# 5V3AUSB.net
KiCad netlist of a schematic drawn in EAGLE
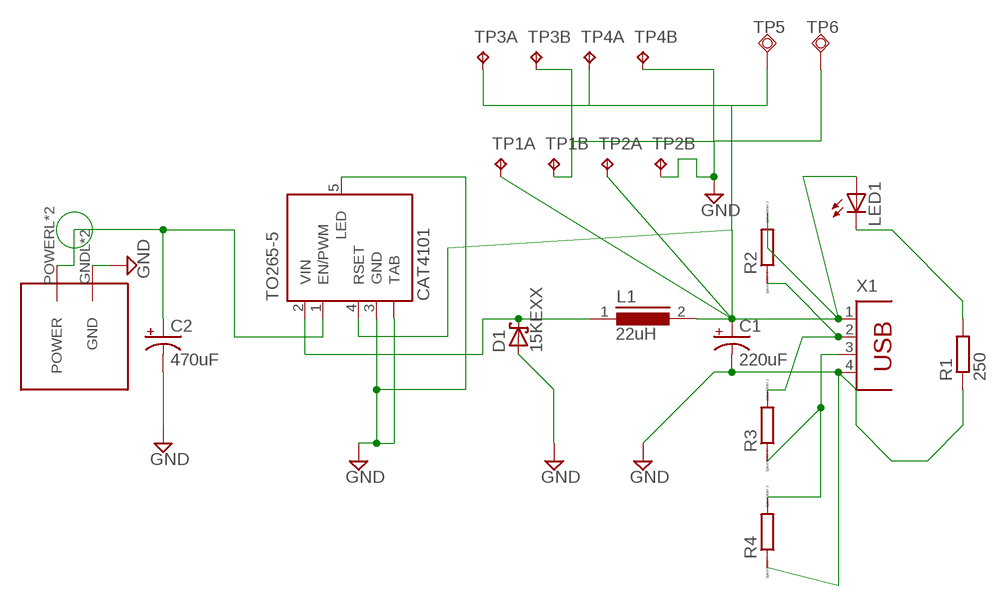
[diagram p0: schematic, sheet 1]

(export (version "E")
  (design (tool "Eeschema 10.0.6"))
  (components
    (comp (ref "C1")
      (value "220uF")
      (footprint "eagle-import:E2,5-6")
      (libsource (lib "eagle-import") (part "CPOL-USE2.5-6"))
    )
    (comp (ref "C2")
      (value "470uF")
      (footprint "eagle-import:E2,5-6")
      (libsource (lib "eagle-import") (part "CPOL-USE2.5-6"))
    )
    (comp (ref "D1")
      (value "15KEXX")
      (footprint "eagle-import:CB429-17")
      (libsource (lib "eagle-import") (part "15KEXX"))
    )
    (comp (ref "L1")
      (value "22uH")
      (footprint "eagle-import:SUKW3-27")
      (libsource (lib "eagle-import") (part "B82133"))
    )
    (comp (ref "LED1")
      (value "LEDCHIPLED_1206")
      (footprint "eagle-import:CHIPLED_1206")
      (libsource (lib "eagle-import") (part "LEDCHIPLED_1206"))
    )
    (comp (ref "R1")
      (value "250")
      (footprint "eagle-import:R1206")
      (libsource (lib "eagle-import") (part "R-EU_R1206"))
    )
    (comp (ref "R2")
      (value "R0204/7")
      (footprint "eagle-import:0204_7")
      (libsource (lib "eagle-import") (part "R0204/7"))
    )
    (comp (ref "R3")
      (value "R0204/7")
      (footprint "eagle-import:0204_7")
      (libsource (lib "eagle-import") (part "R0204/7"))
    )
    (comp (ref "R4")
      (value "R0204/7")
      (footprint "eagle-import:0204_7")
      (libsource (lib "eagle-import") (part "R0204/7"))
    )
    (comp (ref "TO265-5")
      (value "CAT4101")
      (footprint "eagle-import:TO263_5")
      (fields (field (name "MPN") "CAT4101TV-T75"))
      (libsource (lib "eagle-import") (part "CAT4101"))
    )
    (comp (ref "TP1")
      (value "TP2P2-38-20")
      (footprint "eagle-import:P2-38-20")
      (libsource (lib "eagle-import") (part "TP2P2-38-20"))
    )
    (comp (ref "TP2")
      (value "TP2P2-38-20")
      (footprint "eagle-import:P2-38-20")
      (libsource (lib "eagle-import") (part "TP2P2-38-20"))
    )
    (comp (ref "TP3")
      (value "TP2P2-38-20")
      (footprint "eagle-import:P2-38-20")
      (libsource (lib "eagle-import") (part "TP2P2-38-20"))
    )
    (comp (ref "TP4")
      (value "TP2P2-38-20")
      (footprint "eagle-import:P2-38-20")
      (libsource (lib "eagle-import") (part "TP2P2-38-20"))
    )
    (comp (ref "TP5")
      (value "TPSQTP20R")
      (footprint "eagle-import:TP20R")
      (libsource (lib "eagle-import") (part "TPSQTP20R"))
    )
    (comp (ref "TP6")
      (value "TPSQTP20R")
      (footprint "eagle-import:TP20R")
      (libsource (lib "eagle-import") (part "TPSQTP20R"))
    )
    (comp (ref "U$1")
      (value "2X2-MOLEX")
      (footprint "eagle-import:2X2MOLEX")
      (libsource (lib "eagle-import") (part "2X2-MOLEX"))
    )
    (comp (ref "X1")
      (value "PN87520")
      (footprint "eagle-import:PN87520")
      (libsource (lib "eagle-import") (part "PN87520"))
    )
  )
  (nets
    (net (code "1") (name "GND") (class "Default")
      (node (ref "C1") (pin "-") (pinfunction "-_-") (pintype "passive"))
      (node (ref "C2") (pin "-") (pinfunction "-_-") (pintype "passive"))
      (node (ref "D1") (pin "A") (pinfunction "A_A") (pintype "passive"))
      (node (ref "R1") (pin "1") (pinfunction "1_1") (pintype "passive"))
      (node (ref "R4") (pin "1") (pinfunction "1_1") (pintype "passive"))
      (node (ref "TO265-5") (pin "3") (pinfunction "GND_3") (pintype "power_in"))
      (node (ref "TO265-5") (pin "5") (pinfunction "LED_5") (pintype "power_in"))
      (node (ref "TO265-5") (pin "TAB") (pinfunction "TAB_TAB") (pintype "passive"))
      (node (ref "TP1") (pin "TP-2") (pinfunction "TP_TP-2") (pintype "input"))
      (node (ref "TP2") (pin "TP-2") (pinfunction "TP_TP-2") (pintype "input"))
      (node (ref "TP3") (pin "TP-2") (pinfunction "TP_TP-2") (pintype "input"))
      (node (ref "TP4") (pin "TP-2") (pinfunction "TP_TP-2") (pintype "input"))
      (node (ref "TP6") (pin "TP") (pinfunction "TP_TP") (pintype "input"))
      (node (ref "U$1") (pin "GNDL") (pinfunction "GND_GNDL") (pintype "bidirectional"))
      (node (ref "U$1") (pin "GNDR") (pinfunction "GND_GNDR") (pintype "bidirectional"))
      (node (ref "X1") (pin "4") (pinfunction "4_4") (pintype "passive"))
    )
    (net (code "2") (name "Net-(LED1-PadC)") (class "Default")
      (node (ref "LED1") (pin "C") (pinfunction "C_C") (pintype "passive"))
      (node (ref "R1") (pin "2") (pinfunction "2_2") (pintype "passive"))
    )
    (net (code "3") (name "Net-(R2-Pad1)") (class "Default")
      (node (ref "R2") (pin "1") (pinfunction "1_1") (pintype "passive"))
      (node (ref "R3") (pin "2") (pinfunction "2_2") (pintype "passive"))
      (node (ref "X1") (pin "2") (pinfunction "2_2") (pintype "passive"))
    )
    (net (code "4") (name "Net-(R3-Pad1)") (class "Default")
      (node (ref "R3") (pin "1") (pinfunction "1_1") (pintype "passive"))
      (node (ref "R4") (pin "2") (pinfunction "2_2") (pintype "passive"))
      (node (ref "X1") (pin "3") (pinfunction "3_3") (pintype "passive"))
    )
    (net (code "5") (name "Net-(TO265-5-EN{slash}PWM)") (class "Default")
      (node (ref "C2") (pin "+") (pinfunction "+_+") (pintype "passive"))
      (node (ref "TO265-5") (pin "1") (pinfunction "EN/PWM_1") (pintype "input"))
      (node (ref "U$1") (pin "POWERL") (pinfunction "POWER_POWERL") (pintype "bidirectional"))
      (node (ref "U$1") (pin "POWERR") (pinfunction "POWER_POWERR") (pintype "bidirectional"))
    )
    (net (code "6") (name "Net-(TO265-5-RSET)") (class "Default")
      (node (ref "C1") (pin "+") (pinfunction "+_+") (pintype "passive"))
      (node (ref "L1") (pin "2") (pinfunction "2_2") (pintype "passive"))
      (node (ref "LED1") (pin "A") (pinfunction "A_A") (pintype "passive"))
      (node (ref "R2") (pin "2") (pinfunction "2_2") (pintype "passive"))
      (node (ref "TO265-5") (pin "4") (pinfunction "RSET_4") (pintype "input"))
      (node (ref "TP1") (pin "TP-1") (pinfunction "TP_TP-1") (pintype "input"))
      (node (ref "TP2") (pin "TP-1") (pinfunction "TP_TP-1") (pintype "input"))
      (node (ref "TP3") (pin "TP-1") (pinfunction "TP_TP-1") (pintype "input"))
      (node (ref "TP4") (pin "TP-1") (pinfunction "TP_TP-1") (pintype "input"))
      (node (ref "TP5") (pin "TP") (pinfunction "TP_TP") (pintype "input"))
      (node (ref "X1") (pin "1") (pinfunction "1_1") (pintype "passive"))
    )
    (net (code "7") (name "Net-(TO265-5-VIN)") (class "Default")
      (node (ref "D1") (pin "C") (pinfunction "C_C") (pintype "passive"))
      (node (ref "L1") (pin "1") (pinfunction "1_1") (pintype "passive"))
      (node (ref "TO265-5") (pin "2") (pinfunction "VIN_2") (pintype "input"))
    )
  )
)
